# k26_baseboard_usb.net
KiCad netlist of a schematic drawn in Altium Designer
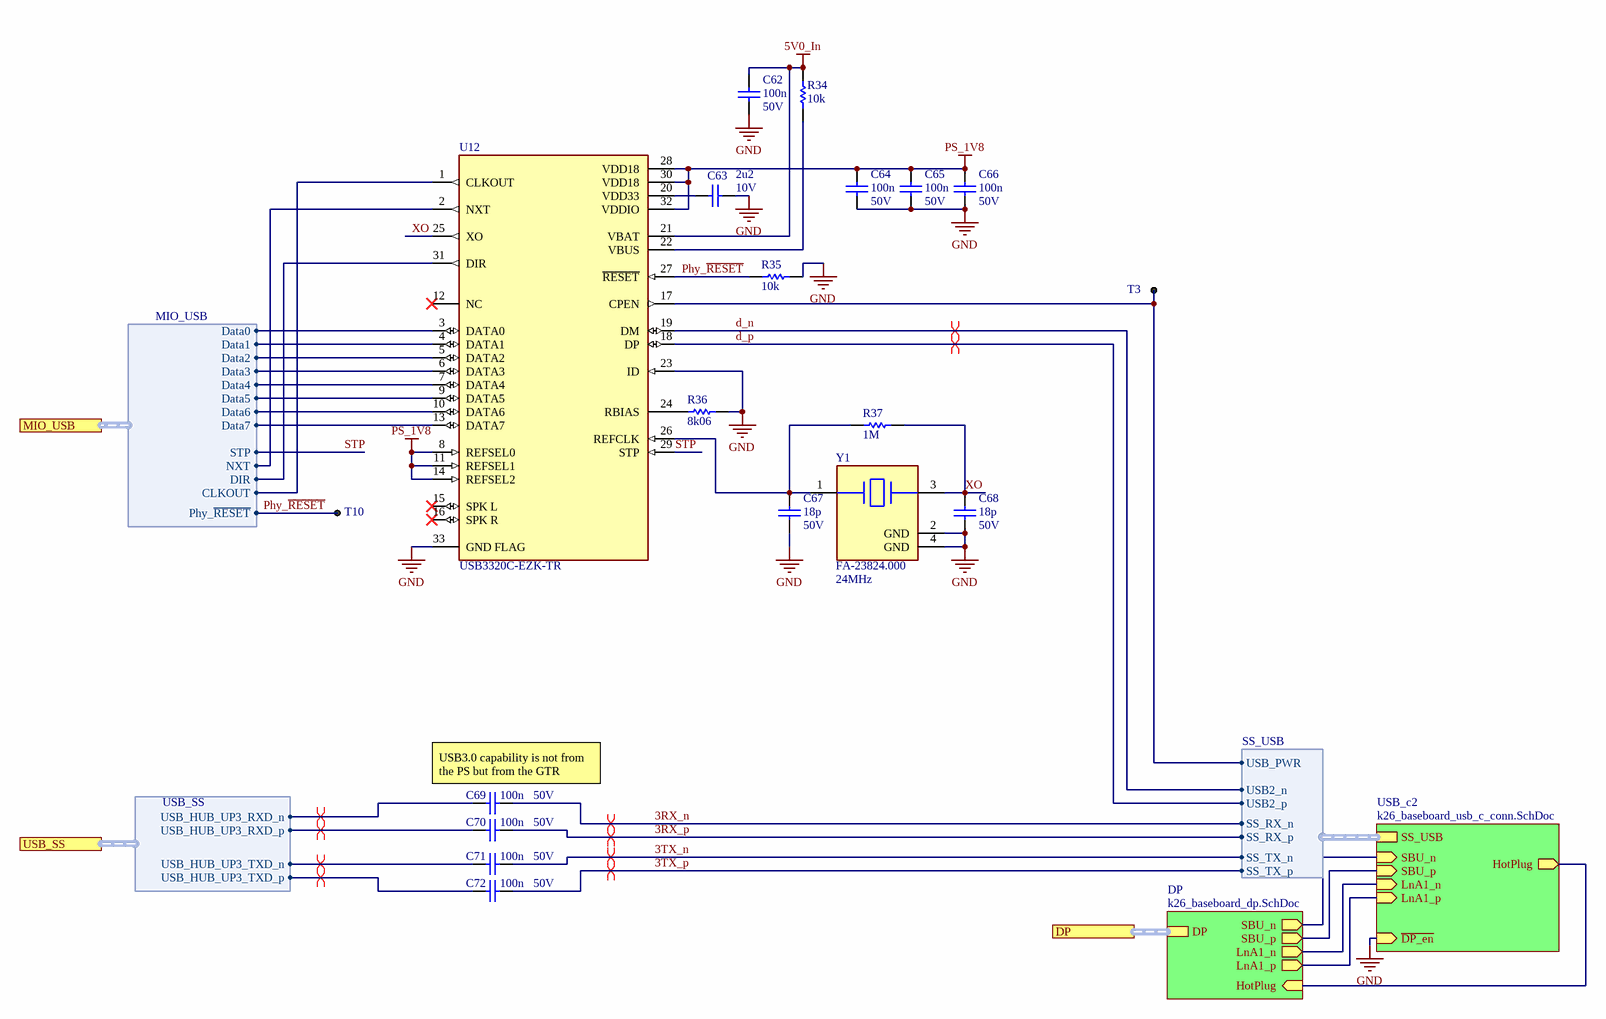
[diagram p0: k26_baseboard_usb.SchDoc]

(export (version "E")
  (design (tool "Eeschema 10.0.6"))
  (components
    (comp (ref "C62")
      (value "100n")
      (footprint "k26_FPGA_drone_baseboard:CAPC0402")
      (fields
        (field (name "MANUFACTURER") "Yageo")
        (field (name "MANUFACTURER PART NUMBER") "CC0402KRX5R9BB104")
        (field (name "RATED DC VOLTAGE (URDC)") "50V")
      )
      (libsource (lib "k26_FPGA_drone_baseboard") (part "cap0402"))
    )
    (comp (ref "C63")
      (value "2u2")
      (footprint "k26_FPGA_drone_baseboard:CAPC0402")
      (fields
        (field (name "MANUFACTURER") "TDK")
        (field (name "MANUFACTURER PART NUMBER") "C1005X7S1A225K050BC")
        (field (name "RATED DC VOLTAGE (URDC)") "10V")
      )
      (libsource (lib "k26_FPGA_drone_baseboard") (part "cap0402"))
    )
    (comp (ref "C64")
      (value "100n")
      (footprint "k26_FPGA_drone_baseboard:CAPC0402")
      (fields
        (field (name "MANUFACTURER") "Yageo")
        (field (name "MANUFACTURER PART NUMBER") "CC0402KRX5R9BB104")
        (field (name "RATED DC VOLTAGE (URDC)") "50V")
      )
      (libsource (lib "k26_FPGA_drone_baseboard") (part "cap0402"))
    )
    (comp (ref "C65")
      (value "100n")
      (footprint "k26_FPGA_drone_baseboard:CAPC0402")
      (fields
        (field (name "MANUFACTURER") "Yageo")
        (field (name "MANUFACTURER PART NUMBER") "CC0402KRX5R9BB104")
        (field (name "RATED DC VOLTAGE (URDC)") "50V")
      )
      (libsource (lib "k26_FPGA_drone_baseboard") (part "cap0402"))
    )
    (comp (ref "C66")
      (value "100n")
      (footprint "k26_FPGA_drone_baseboard:CAPC0402")
      (fields
        (field (name "MANUFACTURER") "Yageo")
        (field (name "MANUFACTURER PART NUMBER") "CC0402KRX5R9BB104")
        (field (name "RATED DC VOLTAGE (URDC)") "50V")
      )
      (libsource (lib "k26_FPGA_drone_baseboard") (part "cap0402"))
    )
    (comp (ref "C67")
      (value "18p")
      (footprint "k26_FPGA_drone_baseboard:CAPC0402")
      (fields
        (field (name "MANUFACTURER") "Murata")
        (field (name "MANUFACTURER PART NUMBER") "GRM1555C1H180JA01D")
        (field (name "RATED DC VOLTAGE (URDC)") "50V")
      )
      (libsource (lib "k26_FPGA_drone_baseboard") (part "cap0402"))
    )
    (comp (ref "C68")
      (value "18p")
      (footprint "k26_FPGA_drone_baseboard:CAPC0402")
      (fields
        (field (name "MANUFACTURER") "Murata")
        (field (name "MANUFACTURER PART NUMBER") "GRM1555C1H180JA01D")
        (field (name "RATED DC VOLTAGE (URDC)") "50V")
      )
      (libsource (lib "k26_FPGA_drone_baseboard") (part "cap0402"))
    )
    (comp (ref "C69")
      (value "100n")
      (footprint "k26_FPGA_drone_baseboard:CAPC0402")
      (fields
        (field (name "MANUFACTURER") "Yageo")
        (field (name "MANUFACTURER PART NUMBER") "CC0402KRX5R9BB104")
        (field (name "RATED DC VOLTAGE (URDC)") "50V")
      )
      (libsource (lib "k26_FPGA_drone_baseboard") (part "cap0402"))
    )
    (comp (ref "C70")
      (value "100n")
      (footprint "k26_FPGA_drone_baseboard:CAPC0402")
      (fields
        (field (name "MANUFACTURER") "Yageo")
        (field (name "MANUFACTURER PART NUMBER") "CC0402KRX5R9BB104")
        (field (name "RATED DC VOLTAGE (URDC)") "50V")
      )
      (libsource (lib "k26_FPGA_drone_baseboard") (part "cap0402"))
    )
    (comp (ref "C71")
      (value "100n")
      (footprint "k26_FPGA_drone_baseboard:CAPC0402")
      (fields
        (field (name "MANUFACTURER") "Yageo")
        (field (name "MANUFACTURER PART NUMBER") "CC0402KRX5R9BB104")
        (field (name "RATED DC VOLTAGE (URDC)") "50V")
      )
      (libsource (lib "k26_FPGA_drone_baseboard") (part "cap0402"))
    )
    (comp (ref "C72")
      (value "100n")
      (footprint "k26_FPGA_drone_baseboard:CAPC0402")
      (fields
        (field (name "MANUFACTURER") "Yageo")
        (field (name "MANUFACTURER PART NUMBER") "CC0402KRX5R9BB104")
        (field (name "RATED DC VOLTAGE (URDC)") "50V")
      )
      (libsource (lib "k26_FPGA_drone_baseboard") (part "cap0402"))
    )
    (comp (ref "R34")
      (value "10k")
      (footprint "k26_FPGA_drone_baseboard:RES0402")
      (fields
        (field (name "MANUFACTURER") "Panasonic")
        (field (name "MANUFACTURER PART NUMBER") "ERJ-2RKF1002X")
        (field (name "TOLERANCE") "1%")
      )
      (libsource (lib "k26_FPGA_drone_baseboard") (part "res0402"))
    )
    (comp (ref "R35")
      (value "10k")
      (footprint "k26_FPGA_drone_baseboard:RES0402")
      (fields
        (field (name "MANUFACTURER") "Panasonic")
        (field (name "MANUFACTURER PART NUMBER") "ERJ-2RKF1002X")
        (field (name "TOLERANCE") "1%")
      )
      (libsource (lib "k26_FPGA_drone_baseboard") (part "res0402"))
    )
    (comp (ref "R36")
      (value "8k06")
      (footprint "k26_FPGA_drone_baseboard:RES0402")
      (fields
        (field (name "MANUFACTURER") "Vishay")
        (field (name "MANUFACTURER PART NUMBER") "CRCW04028K06FKED")
        (field (name "TOLERANCE") "1%")
      )
      (libsource (lib "k26_FPGA_drone_baseboard") (part "res0402"))
    )
    (comp (ref "R37")
      (value "1M")
      (footprint "k26_FPGA_drone_baseboard:RES0402")
      (fields
        (field (name "MANUFACTURER") "Panasonic")
        (field (name "MANUFACTURER PART NUMBER") "ERJ-2GEJ106X")
        (field (name "TOLERANCE") "5%")
      )
      (libsource (lib "k26_FPGA_drone_baseboard") (part "res0402"))
    )
    (comp (ref "T3")
      (value "~")
      (footprint "Pad-1mm")
      (description "1mm SMT Test Pad")
      (libsource (lib "k26_FPGA_drone_baseboard") (part "Test Pad"))
    )
    (comp (ref "T10")
      (value "~")
      (footprint "Pad-1mm")
      (description "1mm SMT Test Pad")
      (libsource (lib "k26_FPGA_drone_baseboard") (part "Test Pad"))
    )
    (comp (ref "U12")
      (value "USB3320C-EZK-TR")
      (footprint "FP-32QFN-3304-5X5B-IPC_C")
      (description "IC TRANSCEIVER HALF 1/1 32QFN")
      (fields
        (field (name "MANUFACTURER") "Microchip")
        (field (name "OCTOPART") "https://octopart.com/usb3320c-ezk-tr-microchip-24995468")
      )
      (libsource (lib "k26_FPGA_drone_baseboard") (part "CMP-0186-00336-2"))
    )
    (comp (ref "Y1")
      (value "FA-23824.000")
      (footprint "FP-FA-238_27_0000MB-C3-MFG")
      (description "CRYSTAL 24.0000MHZ")
      (fields
        (field (name "OCTOPART") "https://octopart.com/fa-238+27.0000mb-c3-epson-42855148")
        (field (name "MANUFACTURER") "Epson")
        (field (name "FREQUENCY") "24MHz")
      )
      (libsource (lib "k26_FPGA_drone_baseboard") (part "CMP-36405-000008-1"))
    )
  )
  (nets
    (net (code "5") (name "/3RX_n") (class "Default")
      (node (ref "C69") (pin "1") (pinfunction "1_1") (pintype "passive"))
    )
    (net (code "6") (name "/3RX_p") (class "Default")
      (node (ref "C70") (pin "1") (pinfunction "1_1") (pintype "passive"))
    )
    (net (code "7") (name "/3TX_n") (class "Default")
      (node (ref "C71") (pin "1") (pinfunction "1_1") (pintype "passive"))
    )
    (net (code "8") (name "/3TX_p") (class "Default")
      (node (ref "C72") (pin "1") (pinfunction "1_1") (pintype "passive"))
    )
    (net (code "9") (name "/CLKOUT") (class "Default")
      (node (ref "U12") (pin "1") (pinfunction "CLKOUT_1") (pintype "output"))
    )
    (net (code "10") (name "/DIR") (class "Default")
      (node (ref "U12") (pin "31") (pinfunction "DIR_31") (pintype "output"))
    )
    (net (code "12") (name "/Data0") (class "Default")
      (node (ref "U12") (pin "3") (pinfunction "DATA0_3") (pintype "bidirectional"))
    )
    (net (code "13") (name "/Data1") (class "Default")
      (node (ref "U12") (pin "4") (pinfunction "DATA1_4") (pintype "bidirectional"))
    )
    (net (code "14") (name "/Data2") (class "Default")
      (node (ref "U12") (pin "5") (pinfunction "DATA2_5") (pintype "bidirectional"))
    )
    (net (code "15") (name "/Data3") (class "Default")
      (node (ref "U12") (pin "6") (pinfunction "DATA3_6") (pintype "bidirectional"))
    )
    (net (code "16") (name "/Data4") (class "Default")
      (node (ref "U12") (pin "7") (pinfunction "DATA4_7") (pintype "bidirectional"))
    )
    (net (code "17") (name "/Data5") (class "Default")
      (node (ref "U12") (pin "9") (pinfunction "DATA5_9") (pintype "bidirectional"))
    )
    (net (code "18") (name "/Data6") (class "Default")
      (node (ref "U12") (pin "10") (pinfunction "DATA6_10") (pintype "bidirectional"))
    )
    (net (code "19") (name "/Data7") (class "Default")
      (node (ref "U12") (pin "13") (pinfunction "DATA7_13") (pintype "bidirectional"))
    )
    (net (code "23") (name "/NXT") (class "Default")
      (node (ref "U12") (pin "2") (pinfunction "NXT_2") (pintype "output"))
    )
    (net (code "24") (name "/Phy_~{RESET}") (class "Default")
      (node (ref "R35") (pin "1") (pinfunction "1_1") (pintype "passive"))
      (node (ref "T10") (pin "1") (pinfunction "1_1") (pintype "passive"))
      (node (ref "U12") (pin "27") (pinfunction "~{RESET}_27") (pintype "input"))
    )
    (net (code "27") (name "/STP") (class "Default")
      (node (ref "U12") (pin "29") (pinfunction "STP_29") (pintype "input"))
    )
    (net (code "28") (name "/USB_HUB_UP3_RXD_n") (class "Default")
      (node (ref "C69") (pin "2") (pinfunction "2_2") (pintype "passive"))
    )
    (net (code "29") (name "/USB_HUB_UP3_RXD_p") (class "Default")
      (node (ref "C70") (pin "2") (pinfunction "2_2") (pintype "passive"))
    )
    (net (code "30") (name "/USB_HUB_UP3_TXD_n") (class "Default")
      (node (ref "C71") (pin "2") (pinfunction "2_2") (pintype "passive"))
    )
    (net (code "31") (name "/USB_HUB_UP3_TXD_p") (class "Default")
      (node (ref "C72") (pin "2") (pinfunction "2_2") (pintype "passive"))
    )
    (net (code "32") (name "/USB_PWR") (class "Default")
      (node (ref "T3") (pin "1") (pinfunction "1_1") (pintype "passive"))
      (node (ref "U12") (pin "17") (pinfunction "CPEN_17") (pintype "output"))
    )
    (net (code "33") (name "/XO") (class "Default")
      (node (ref "C68") (pin "2") (pinfunction "2_2") (pintype "passive"))
      (node (ref "R37") (pin "2") (pinfunction "2_2") (pintype "passive"))
      (node (ref "U12") (pin "25") (pinfunction "XO_25") (pintype "output"))
      (node (ref "Y1") (pin "3") (pinfunction "3_3") (pintype "passive"))
    )
    (net (code "34") (name "/d_n") (class "Default")
      (node (ref "U12") (pin "19") (pinfunction "DM_19") (pintype "bidirectional"))
    )
    (net (code "35") (name "/d_p") (class "Default")
      (node (ref "U12") (pin "18") (pinfunction "DP_18") (pintype "bidirectional"))
    )
    (net (code "39") (name "5V0_In") (class "Default")
      (node (ref "C62") (pin "2") (pinfunction "2_2") (pintype "passive"))
      (node (ref "R34") (pin "2") (pinfunction "2_2") (pintype "passive"))
      (node (ref "U12") (pin "21") (pinfunction "VBAT_21") (pintype "power_in"))
    )
    (net (code "40") (name "GND") (class "Default")
      (node (ref "C62") (pin "1") (pinfunction "1_1") (pintype "passive"))
      (node (ref "C63") (pin "1") (pinfunction "1_1") (pintype "passive"))
      (node (ref "C64") (pin "1") (pinfunction "1_1") (pintype "passive"))
      (node (ref "C65") (pin "1") (pinfunction "1_1") (pintype "passive"))
      (node (ref "C66") (pin "1") (pinfunction "1_1") (pintype "passive"))
      (node (ref "C67") (pin "1") (pinfunction "1_1") (pintype "passive"))
      (node (ref "C68") (pin "1") (pinfunction "1_1") (pintype "passive"))
      (node (ref "R35") (pin "2") (pinfunction "2_2") (pintype "passive"))
      (node (ref "R36") (pin "1") (pinfunction "1_1") (pintype "passive"))
      (node (ref "U12") (pin "23") (pinfunction "ID_23") (pintype "input"))
      (node (ref "U12") (pin "33") (pinfunction "GND_FLAG_33") (pintype "power_in"))
      (node (ref "Y1") (pin "2") (pinfunction "GND_2") (pintype "power_in"))
      (node (ref "Y1") (pin "4") (pinfunction "GND_4") (pintype "power_in"))
    )
    (net (code "41") (name "Net-(U12-RBIAS)") (class "Default")
      (node (ref "R36") (pin "2") (pinfunction "2_2") (pintype "passive"))
      (node (ref "U12") (pin "24") (pinfunction "RBIAS_24") (pintype "power_in"))
    )
    (net (code "42") (name "Net-(U12-REFCLK)") (class "Default")
      (node (ref "C67") (pin "2") (pinfunction "2_2") (pintype "passive"))
      (node (ref "R37") (pin "1") (pinfunction "1_1") (pintype "passive"))
      (node (ref "U12") (pin "26") (pinfunction "REFCLK_26") (pintype "input"))
      (node (ref "Y1") (pin "1") (pinfunction "1_1") (pintype "passive"))
    )
    (net (code "43") (name "Net-(U12-VBUS)") (class "Default")
      (node (ref "R34") (pin "1") (pinfunction "1_1") (pintype "passive"))
      (node (ref "U12") (pin "22") (pinfunction "VBUS_22") (pintype "power_in"))
    )
    (net (code "44") (name "Net-(U12-VDD33)") (class "Default")
      (node (ref "C63") (pin "2") (pinfunction "2_2") (pintype "passive"))
      (node (ref "U12") (pin "20") (pinfunction "VDD33_20") (pintype "power_in"))
    )
    (net (code "45") (name "PS_1V8") (class "Default")
      (node (ref "C64") (pin "2") (pinfunction "2_2") (pintype "passive"))
      (node (ref "C65") (pin "2") (pinfunction "2_2") (pintype "passive"))
      (node (ref "C66") (pin "2") (pinfunction "2_2") (pintype "passive"))
      (node (ref "U12") (pin "11") (pinfunction "REFSEL1_11") (pintype "input"))
      (node (ref "U12") (pin "14") (pinfunction "REFSEL2_14") (pintype "input"))
      (node (ref "U12") (pin "28") (pinfunction "VDD18_28") (pintype "power_in"))
      (node (ref "U12") (pin "30") (pinfunction "VDD18_30") (pintype "power_in"))
      (node (ref "U12") (pin "32") (pinfunction "VDDIO_32") (pintype "power_in"))
      (node (ref "U12") (pin "8") (pinfunction "REFSEL0_8") (pintype "input"))
    )
    (net (code "46") (name "unconnected-(U12-NC-Pad12)") (class "Default")
      (node (ref "U12") (pin "12") (pinfunction "NC_12") (pintype "passive+no_connect"))
    )
    (net (code "47") (name "unconnected-(U12-SPK_L-Pad15)") (class "Default")
      (node (ref "U12") (pin "15") (pinfunction "SPK_L_15") (pintype "bidirectional+no_connect"))
    )
    (net (code "48") (name "unconnected-(U12-SPK_R-Pad16)") (class "Default")
      (node (ref "U12") (pin "16") (pinfunction "SPK_R_16") (pintype "bidirectional+no_connect"))
    )
  )
)
